# rng.net
KiCad netlist of a schematic drawn in EAGLE
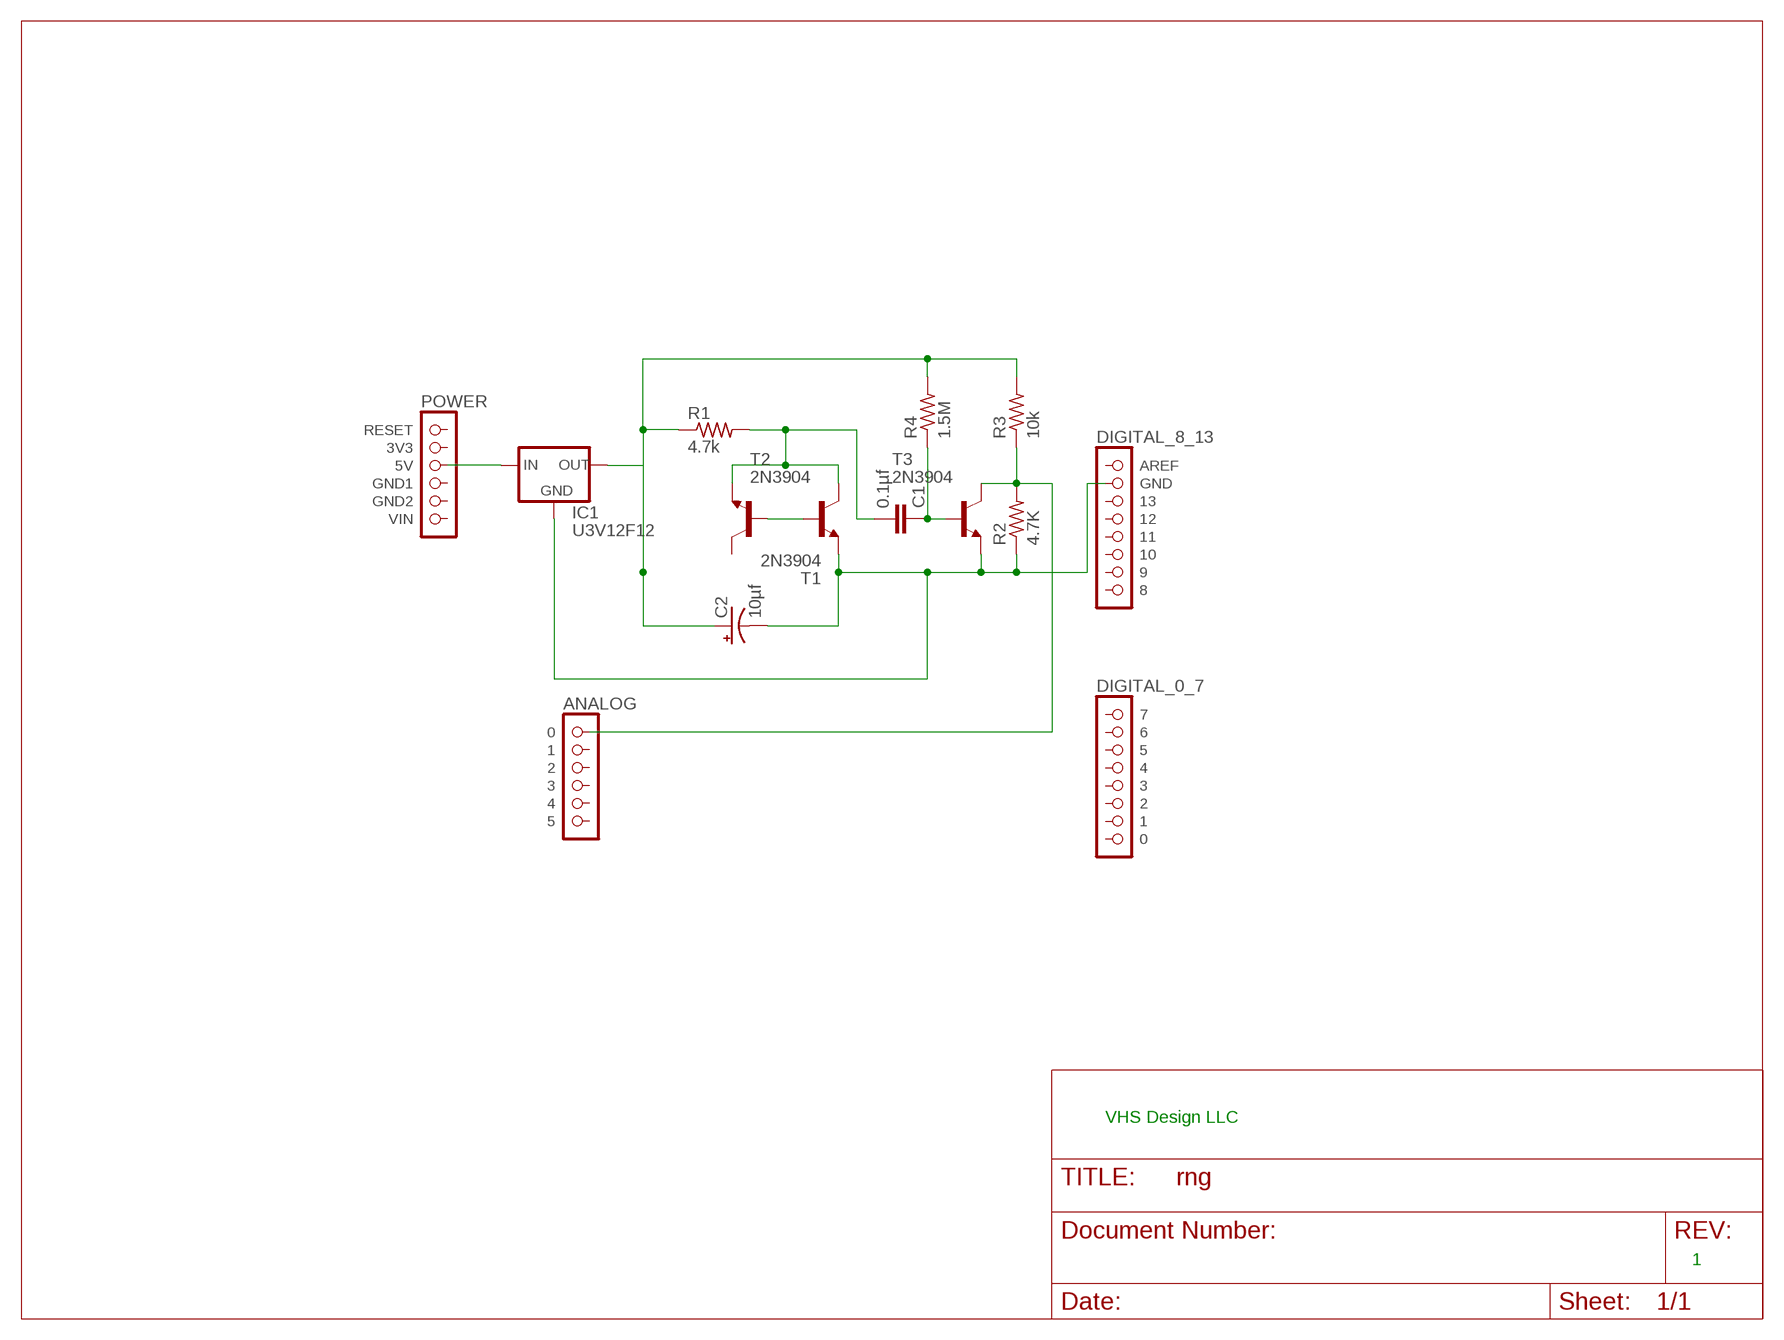
[diagram p0: schematic, sheet 1]

(export (version "E")
  (design (tool "Eeschema 10.0.6"))
  (components
    (comp (ref "C1")
      (value "0.1µf")
      (footprint "eagle-import:C7.5B3")
      (libsource (lib "eagle-import") (part "C7.5/3"))
    )
    (comp (ref "C2")
      (value "10µf")
      (footprint "eagle-import:E2,5-6")
      (libsource (lib "eagle-import") (part "CPOL-USE2.5-6"))
    )
    (comp (ref "IC1")
      (value "U3V12F12")
      (footprint "eagle-import:78XXS")
      (libsource (lib "eagle-import") (part "78XXS"))
    )
    (comp (ref "R1")
      (value "4.7k")
      (footprint "eagle-import:0204_7")
      (libsource (lib "eagle-import") (part "R-US_0204/7"))
    )
    (comp (ref "R2")
      (value "4.7K")
      (footprint "eagle-import:0204_7")
      (libsource (lib "eagle-import") (part "R-US_0204/7"))
    )
    (comp (ref "R3")
      (value "10k")
      (footprint "eagle-import:0204_7")
      (libsource (lib "eagle-import") (part "R-US_0204/7"))
    )
    (comp (ref "R4")
      (value "1.5M")
      (footprint "eagle-import:0204_7")
      (libsource (lib "eagle-import") (part "R-US_0204/7"))
    )
    (comp (ref "T1")
      (value "2N3904")
      (footprint "eagle-import:TO92")
      (libsource (lib "eagle-import") (part "2N3904"))
    )
    (comp (ref "T2")
      (value "2N3904")
      (footprint "eagle-import:TO92")
      (libsource (lib "eagle-import") (part "2N3904"))
    )
    (comp (ref "T3")
      (value "2N3904")
      (footprint "eagle-import:TO92")
      (libsource (lib "eagle-import") (part "2N3904"))
    )
    (comp (ref "U$1")
      (value "POWER")
      (footprint "eagle-import:1X06")
      (libsource (lib "eagle-import") (part "POWER"))
    )
    (comp (ref "U$2")
      (value "ANALOG")
      (footprint "eagle-import:1X06")
      (libsource (lib "eagle-import") (part "ANALOG"))
    )
    (comp (ref "U$3")
      (value "DIGITAL_0_7")
      (footprint "eagle-import:1X08")
      (libsource (lib "eagle-import") (part "DIGITAL_0_7"))
    )
    (comp (ref "U$4")
      (value "DIGITAL_8_13")
      (footprint "eagle-import:1X08")
      (libsource (lib "eagle-import") (part "DIGITAL_8_13"))
    )
  )
  (nets
    (net (code "1") (name "Net-(C2-Pad+)") (class "Default")
      (node (ref "C2") (pin "+") (pinfunction "+_+") (pintype "passive"))
      (node (ref "IC1") (pin "OUT") (pinfunction "OUT_OUT") (pintype "passive"))
      (node (ref "R1") (pin "1") (pinfunction "1_1") (pintype "passive"))
      (node (ref "R3") (pin "2") (pinfunction "2_2") (pintype "passive"))
      (node (ref "R4") (pin "2") (pinfunction "2_2") (pintype "passive"))
    )
    (net (code "2") (name "Net-(T1-B)") (class "Default")
      (node (ref "T1") (pin "2") (pinfunction "B_2") (pintype "passive"))
      (node (ref "T2") (pin "2") (pinfunction "B_2") (pintype "passive"))
    )
    (net (code "3") (name "Net-(T1-E)") (class "Default")
      (node (ref "C1") (pin "2") (pinfunction "2_2") (pintype "passive"))
      (node (ref "R1") (pin "2") (pinfunction "2_2") (pintype "passive"))
      (node (ref "T1") (pin "3") (pinfunction "E_3") (pintype "passive"))
      (node (ref "T2") (pin "1") (pinfunction "C_1") (pintype "passive"))
    )
    (net (code "4") (name "Net-(T2-E)") (class "Default")
      (node (ref "C2") (pin "-") (pinfunction "-_-") (pintype "passive"))
      (node (ref "IC1") (pin "GND") (pinfunction "GND_GND") (pintype "input"))
      (node (ref "R2") (pin "1") (pinfunction "1_1") (pintype "passive"))
      (node (ref "T2") (pin "3") (pinfunction "E_3") (pintype "passive"))
      (node (ref "T3") (pin "3") (pinfunction "E_3") (pintype "passive"))
      (node (ref "U$4") (pin "2") (pinfunction "GND_2") (pintype "passive"))
    )
    (net (code "5") (name "Net-(T3-B)") (class "Default")
      (node (ref "C1") (pin "1") (pinfunction "1_1") (pintype "passive"))
      (node (ref "R4") (pin "1") (pinfunction "1_1") (pintype "passive"))
      (node (ref "T3") (pin "2") (pinfunction "B_2") (pintype "passive"))
    )
    (net (code "6") (name "Net-(T3-C)") (class "Default")
      (node (ref "R2") (pin "2") (pinfunction "2_2") (pintype "passive"))
      (node (ref "R3") (pin "1") (pinfunction "1_1") (pintype "passive"))
      (node (ref "T3") (pin "1") (pinfunction "C_1") (pintype "passive"))
      (node (ref "U$2") (pin "1") (pinfunction "0_1") (pintype "passive"))
    )
    (net (code "7") (name "Net-(U$1-5V)") (class "Default")
      (node (ref "IC1") (pin "IN") (pinfunction "IN_IN") (pintype "input"))
      (node (ref "U$1") (pin "3") (pinfunction "5V_3") (pintype "passive"))
    )
    (net (code "8") (name "unconnected-(T1-C-Pad1)") (class "Default")
      (node (ref "T1") (pin "1") (pinfunction "C_1") (pintype "passive"))
    )
    (net (code "9") (name "unconnected-(U$1-3V3-Pad2)") (class "Default")
      (node (ref "U$1") (pin "2") (pinfunction "3V3_2") (pintype "passive"))
    )
    (net (code "10") (name "unconnected-(U$1-GND1-Pad4)") (class "Default")
      (node (ref "U$1") (pin "4") (pinfunction "GND1_4") (pintype "passive"))
    )
    (net (code "11") (name "unconnected-(U$1-GND2-Pad5)") (class "Default")
      (node (ref "U$1") (pin "5") (pinfunction "GND2_5") (pintype "passive"))
    )
    (net (code "12") (name "unconnected-(U$1-RESET-Pad1)") (class "Default")
      (node (ref "U$1") (pin "1") (pinfunction "RESET_1") (pintype "passive"))
    )
    (net (code "13") (name "unconnected-(U$1-VIN-Pad6)") (class "Default")
      (node (ref "U$1") (pin "6") (pinfunction "VIN_6") (pintype "passive"))
    )
    (net (code "14") (name "unconnected-(U$2-1-Pad2)") (class "Default")
      (node (ref "U$2") (pin "2") (pinfunction "1_2") (pintype "passive"))
    )
    (net (code "15") (name "unconnected-(U$2-2-Pad3)") (class "Default")
      (node (ref "U$2") (pin "3") (pinfunction "2_3") (pintype "passive"))
    )
    (net (code "16") (name "unconnected-(U$2-3-Pad4)") (class "Default")
      (node (ref "U$2") (pin "4") (pinfunction "3_4") (pintype "passive"))
    )
    (net (code "17") (name "unconnected-(U$2-4-Pad5)") (class "Default")
      (node (ref "U$2") (pin "5") (pinfunction "4_5") (pintype "passive"))
    )
    (net (code "18") (name "unconnected-(U$2-5-Pad6)") (class "Default")
      (node (ref "U$2") (pin "6") (pinfunction "5_6") (pintype "passive"))
    )
    (net (code "19") (name "unconnected-(U$3-0-Pad8)") (class "Default")
      (node (ref "U$3") (pin "8") (pinfunction "0_8") (pintype "passive"))
    )
    (net (code "20") (name "unconnected-(U$3-1-Pad7)") (class "Default")
      (node (ref "U$3") (pin "7") (pinfunction "1_7") (pintype "passive"))
    )
    (net (code "21") (name "unconnected-(U$3-2-Pad6)") (class "Default")
      (node (ref "U$3") (pin "6") (pinfunction "2_6") (pintype "passive"))
    )
    (net (code "22") (name "unconnected-(U$3-3-Pad5)") (class "Default")
      (node (ref "U$3") (pin "5") (pinfunction "3_5") (pintype "passive"))
    )
    (net (code "23") (name "unconnected-(U$3-5-Pad3)") (class "Default")
      (node (ref "U$3") (pin "3") (pinfunction "5_3") (pintype "passive"))
    )
    (net (code "24") (name "unconnected-(U$3-6-Pad2)") (class "Default")
      (node (ref "U$3") (pin "2") (pinfunction "6_2") (pintype "passive"))
    )
    (net (code "25") (name "unconnected-(U$3-7-Pad1)") (class "Default")
      (node (ref "U$3") (pin "1") (pinfunction "7_1") (pintype "passive"))
    )
    (net (code "26") (name "unconnected-(U$3-Pad4)") (class "Default")
      (node (ref "U$3") (pin "4") (pinfunction "4_4") (pintype "passive"))
    )
    (net (code "27") (name "unconnected-(U$4-9-Pad7)") (class "Default")
      (node (ref "U$4") (pin "7") (pinfunction "9_7") (pintype "passive"))
    )
    (net (code "28") (name "unconnected-(U$4-10-Pad6)") (class "Default")
      (node (ref "U$4") (pin "6") (pinfunction "10_6") (pintype "passive"))
    )
    (net (code "29") (name "unconnected-(U$4-11-Pad5)") (class "Default")
      (node (ref "U$4") (pin "5") (pinfunction "11_5") (pintype "passive"))
    )
    (net (code "30") (name "unconnected-(U$4-12-Pad4)") (class "Default")
      (node (ref "U$4") (pin "4") (pinfunction "12_4") (pintype "passive"))
    )
    (net (code "31") (name "unconnected-(U$4-13-Pad3)") (class "Default")
      (node (ref "U$4") (pin "3") (pinfunction "13_3") (pintype "passive"))
    )
    (net (code "32") (name "unconnected-(U$4-AREF-Pad1)") (class "Default")
      (node (ref "U$4") (pin "1") (pinfunction "AREF_1") (pintype "passive"))
    )
    (net (code "33") (name "unconnected-(U$4-Pad8)") (class "Default")
      (node (ref "U$4") (pin "8") (pinfunction "8_8") (pintype "passive"))
    )
  )
)
